# Schematic.net
KiCad netlist of a schematic drawn in EAGLE
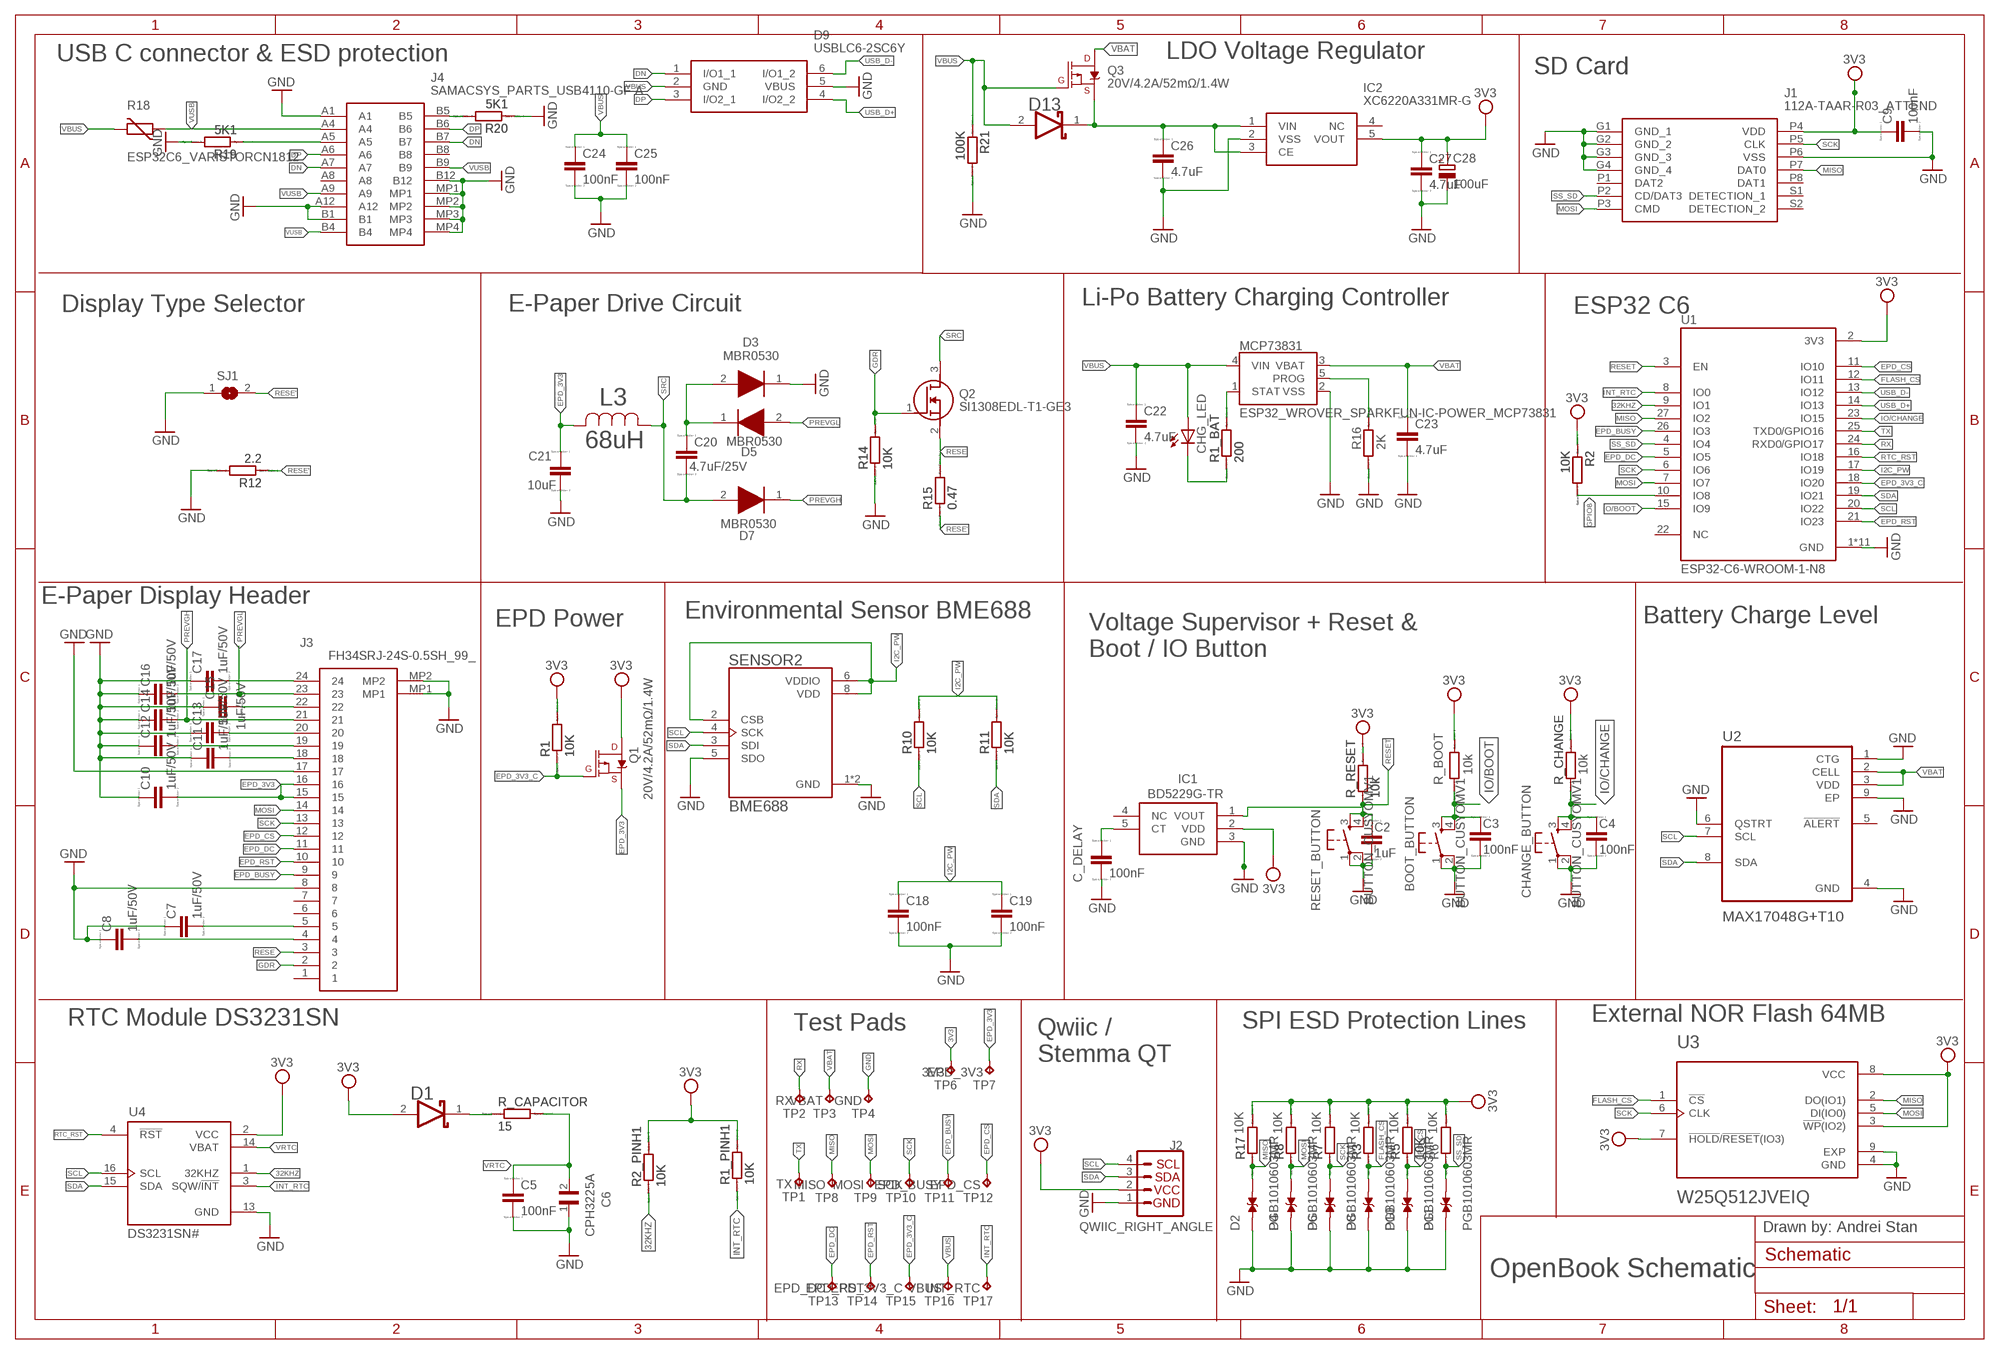
[diagram p0: schematic, sheet 1]

(export (version "E")
  (design (tool "Eeschema 10.0.6"))
  (components
    (comp (ref "BOOT_BUTTON")
      (value "BUTTON_CUSYOMV1")
      (footprint "eagle-import:MYBUTTON")
      (libsource (lib "eagle-import") (part "BUTTON_CUSYOMV1"))
    )
    (comp (ref "C2")
      (value "1uF")
      (footprint "eagle-import:EAGLE-LTSPICE_C0402")
      (libsource (lib "eagle-import") (part "EAGLE-LTSPICE_CC0402"))
    )
    (comp (ref "C3")
      (value "100nF")
      (footprint "eagle-import:EAGLE-LTSPICE_C0402")
      (libsource (lib "eagle-import") (part "EAGLE-LTSPICE_CC0402"))
    )
    (comp (ref "C4")
      (value "100nF")
      (footprint "eagle-import:EAGLE-LTSPICE_C0402")
      (libsource (lib "eagle-import") (part "EAGLE-LTSPICE_CC0402"))
    )
    (comp (ref "C5")
      (value "100nF")
      (footprint "eagle-import:EAGLE-LTSPICE_C0402")
      (libsource (lib "eagle-import") (part "EAGLE-LTSPICE_CC0402"))
    )
    (comp (ref "C6")
      (value "CPH3225A")
      (footprint "eagle-import:CAPCP3225X100N")
      (fields (field (name "MF") "Seiko Instruments"))
      (libsource (lib "eagle-import") (part "CPH3225A"))
    )
    (comp (ref "C7")
      (value "1uF/50V")
      (footprint "eagle-import:EAGLE-LTSPICE_C0402")
      (libsource (lib "eagle-import") (part "EAGLE-LTSPICE_CC0402"))
    )
    (comp (ref "C8")
      (value "1uF/50V")
      (footprint "eagle-import:EAGLE-LTSPICE_C0402")
      (libsource (lib "eagle-import") (part "EAGLE-LTSPICE_CC0402"))
    )
    (comp (ref "C9")
      (value "100nF")
      (footprint "eagle-import:EAGLE-LTSPICE_C0402")
      (libsource (lib "eagle-import") (part "EAGLE-LTSPICE_CC0402"))
    )
    (comp (ref "C10")
      (value "1uF/50V")
      (footprint "eagle-import:EAGLE-LTSPICE_C0402")
      (libsource (lib "eagle-import") (part "EAGLE-LTSPICE_CC0402"))
    )
    (comp (ref "C11")
      (value "1uF/50V")
      (footprint "eagle-import:EAGLE-LTSPICE_C0402")
      (libsource (lib "eagle-import") (part "EAGLE-LTSPICE_CC0402"))
    )
    (comp (ref "C12")
      (value "1uF/50V")
      (footprint "eagle-import:EAGLE-LTSPICE_C0402")
      (libsource (lib "eagle-import") (part "EAGLE-LTSPICE_CC0402"))
    )
    (comp (ref "C13")
      (value "1uF/50V")
      (footprint "eagle-import:EAGLE-LTSPICE_C0402")
      (libsource (lib "eagle-import") (part "EAGLE-LTSPICE_CC0402"))
    )
    (comp (ref "C14")
      (value "1uF/50V")
      (footprint "eagle-import:EAGLE-LTSPICE_C0402")
      (libsource (lib "eagle-import") (part "EAGLE-LTSPICE_CC0402"))
    )
    (comp (ref "C15")
      (value "1uF/50V")
      (footprint "eagle-import:EAGLE-LTSPICE_C0402")
      (libsource (lib "eagle-import") (part "EAGLE-LTSPICE_CC0402"))
    )
    (comp (ref "C16")
      (value "1uF/50V")
      (footprint "eagle-import:EAGLE-LTSPICE_C0402")
      (libsource (lib "eagle-import") (part "EAGLE-LTSPICE_CC0402"))
    )
    (comp (ref "C17")
      (value "1uF/50V")
      (footprint "eagle-import:EAGLE-LTSPICE_C0402")
      (libsource (lib "eagle-import") (part "EAGLE-LTSPICE_CC0402"))
    )
    (comp (ref "C18")
      (value "100nF")
      (footprint "eagle-import:EAGLE-LTSPICE_C0402")
      (libsource (lib "eagle-import") (part "EAGLE-LTSPICE_CC0402"))
    )
    (comp (ref "C19")
      (value "100nF")
      (footprint "eagle-import:EAGLE-LTSPICE_C0402")
      (libsource (lib "eagle-import") (part "EAGLE-LTSPICE_CC0402"))
    )
    (comp (ref "C20")
      (value "4.7uF/25V")
      (footprint "eagle-import:ESP32_WROVER_EAGLE-LTSPICE_C0402")
      (libsource (lib "eagle-import") (part "ESP32_WROVER_EAGLE-LTSPICE_CC0402"))
    )
    (comp (ref "C21")
      (value "10uF")
      (footprint "eagle-import:ESP32_WROVER_EAGLE-LTSPICE_C0402")
      (libsource (lib "eagle-import") (part "ESP32_WROVER_EAGLE-LTSPICE_CC0402"))
    )
    (comp (ref "C22")
      (value "4.7uF")
      (footprint "eagle-import:EAGLE-LTSPICE_C0402")
      (libsource (lib "eagle-import") (part "EAGLE-LTSPICE_CC0402"))
    )
    (comp (ref "C23")
      (value "4.7uF")
      (footprint "eagle-import:EAGLE-LTSPICE_C0402")
      (libsource (lib "eagle-import") (part "EAGLE-LTSPICE_CC0402"))
    )
    (comp (ref "C24")
      (value "100nF")
      (footprint "eagle-import:ESP32_WROVER_EAGLE-LTSPICE_C0402")
      (libsource (lib "eagle-import") (part "ESP32_WROVER_EAGLE-LTSPICE_CC0402"))
    )
    (comp (ref "C25")
      (value "100nF")
      (footprint "eagle-import:ESP32_WROVER_EAGLE-LTSPICE_C0402")
      (libsource (lib "eagle-import") (part "ESP32_WROVER_EAGLE-LTSPICE_CC0402"))
    )
    (comp (ref "C26")
      (value "4.7uF")
      (footprint "eagle-import:ESP32_WROVER_EAGLE-LTSPICE_C0402")
      (libsource (lib "eagle-import") (part "ESP32_WROVER_EAGLE-LTSPICE_CC0402"))
    )
    (comp (ref "C27")
      (value "4.7uF")
      (footprint "eagle-import:ESP32_WROVER_EAGLE-LTSPICE_C0402")
      (libsource (lib "eagle-import") (part "ESP32_WROVER_EAGLE-LTSPICE_CC0402"))
    )
    (comp (ref "C28")
      (value "100uF")
      (footprint "eagle-import:RCL_CT3528")
      (libsource (lib "eagle-import") (part "RCL_CPOL-EUCT3528"))
    )
    (comp (ref "CHANGE_BUTTON")
      (value "BUTTON_CUSYOMV1")
      (footprint "eagle-import:MYBUTTON")
      (libsource (lib "eagle-import") (part "BUTTON_CUSYOMV1"))
    )
    (comp (ref "CHG_LED")
      (value "ADAFRUIT_LEDCHIP-LED0603")
      (footprint "eagle-import:ADAFRUIT_CHIP-LED0603")
      (libsource (lib "eagle-import") (part "ADAFRUIT_LEDCHIP-LED0603"))
    )
    (comp (ref "C_DELAY")
      (value "100nF")
      (footprint "eagle-import:EAGLE-LTSPICE_C0402")
      (libsource (lib "eagle-import") (part "EAGLE-LTSPICE_CC0402"))
    )
    (comp (ref "D1")
      (value "ESP32_WROVER_AVX---SD0805S020S1R0_AVX_SD0805S020S1R0_0_0AVX_SD0805S020S1R0_0_0")
      (footprint "eagle-import:ESP32_WROVER_AVX---SD0805S020S1R0_AVX_SD0805S020S1R0_0")
      (fields
        (field (name "DIGIKEY_PART_NUMBER") "478-7800-1-ND")
        (field (name "MF") "AVX")
        (field (name "MOUSER_PART_NUMBER") "581-SD0805S020S1R0")
      )
      (libsource (lib "eagle-import") (part "ESP32_WROVER_AVX---SD0805S020S1R0_AVX_SD0805S020S1R0_0_0AVX_SD0805S020S1R0_0_0"))
    )
    (comp (ref "D2")
      (value "PGB1010603MR")
      (footprint "eagle-import:DIOC1608X36N")
      (fields (field (name "MF") "Littelfuse Inc."))
      (libsource (lib "eagle-import") (part "PGB1010603MR"))
    )
    (comp (ref "D3")
      (value "MBR0530")
      (footprint "eagle-import:SOD3716X135N")
      (fields (field (name "MF") "ON Semiconductor"))
      (libsource (lib "eagle-import") (part "MBR0530"))
    )
    (comp (ref "D4")
      (value "PGB1010603MR")
      (footprint "eagle-import:DIOC1608X36N")
      (fields (field (name "MF") "Littelfuse Inc."))
      (libsource (lib "eagle-import") (part "PGB1010603MR"))
    )
    (comp (ref "D5")
      (value "MBR0530")
      (footprint "eagle-import:SOD3716X135N")
      (fields (field (name "MF") "ON Semiconductor"))
      (libsource (lib "eagle-import") (part "MBR0530"))
    )
    (comp (ref "D6")
      (value "PGB1010603MR")
      (footprint "eagle-import:DIOC1608X36N")
      (fields (field (name "MF") "Littelfuse Inc."))
      (libsource (lib "eagle-import") (part "PGB1010603MR"))
    )
    (comp (ref "D7")
      (value "MBR0530")
      (footprint "eagle-import:SOD3716X135N")
      (fields (field (name "MF") "ON Semiconductor"))
      (libsource (lib "eagle-import") (part "MBR0530"))
    )
    (comp (ref "D8")
      (value "PGB1010603MR")
      (footprint "eagle-import:DIOC1608X36N")
      (fields (field (name "MF") "Littelfuse Inc."))
      (libsource (lib "eagle-import") (part "PGB1010603MR"))
    )
    (comp (ref "D9")
      (value "USBLC6-2SC6Y")
      (footprint "eagle-import:SOT95P280X145-6N")
      (fields (field (name "MF") "STMicroelectronics"))
      (libsource (lib "eagle-import") (part "USBLC6-2SC6Y"))
    )
    (comp (ref "D10")
      (value "PGB1010603MR")
      (footprint "eagle-import:DIOC1608X36N")
      (fields (field (name "MF") "Littelfuse Inc."))
      (libsource (lib "eagle-import") (part "PGB1010603MR"))
    )
    (comp (ref "D11")
      (value "PGB1010603MR")
      (footprint "eagle-import:DIOC1608X36N")
      (fields (field (name "MF") "Littelfuse Inc."))
      (libsource (lib "eagle-import") (part "PGB1010603MR"))
    )
    (comp (ref "D13")
      (value "ESP32_WROVER_AVX---SD0805S020S1R0_AVX_SD0805S020S1R0_0_0AVX_SD0805S020S1R0_0_0")
      (footprint "eagle-import:ESP32_WROVER_AVX---SD0805S020S1R0_AVX_SD0805S020S1R0_0")
      (fields
        (field (name "DIGIKEY_PART_NUMBER") "478-7800-1-ND")
        (field (name "MF") "AVX")
        (field (name "MOUSER_PART_NUMBER") "581-SD0805S020S1R0")
      )
      (libsource (lib "eagle-import") (part "DeskAssistant v19 v2_vf.c-uWg7zGRE2SlFihlENo6g_ESP32_WROVER_AVX---SD0805S020S1R0_AVX_SD0805S020S1R0_0_0AVX_SD0805S020S1R0_0_0"))
    )
    (comp (ref "IC1")
      (value "BD5229G-TR")
      (footprint "eagle-import:SOT95P280X125-5N")
      (fields (field (name "MOUSER_PART_NUMBER") "755-BD5229G-TR"))
      (libsource (lib "eagle-import") (part "BD5229G-TR"))
    )
    (comp (ref "IC2")
      (value "XC6220A331MR-G")
      (footprint "eagle-import:SOT95P280X120-5N")
      (fields (field (name "MOUSER_PART_NUMBER") "865-XC6220A331MR-G"))
      (libsource (lib "eagle-import") (part "XC6220A331MR-G"))
    )
    (comp (ref "J1")
      (value "112A-TAAR-R03_ATTEND")
      (footprint "eagle-import:112ATAARR03ATTEND")
      (fields (field (name "MANUFACTURER_PART_NUMBER") "112A-TAAR-R03 ATTEND"))
      (libsource (lib "eagle-import") (part "112A-TAAR-R03_ATTEND"))
    )
    (comp (ref "J2")
      (value "QWIIC_RIGHT_ANGLE")
      (footprint "eagle-import:JST04_1MM_RA")
      (libsource (lib "eagle-import") (part "QWIIC_CONNECTORJS-1MM"))
    )
    (comp (ref "J3")
      (value "FH34SRJ-24S-0.5SH_99_")
      (footprint "eagle-import:FH34SRJ24S05SH99")
      (fields
        (field (name "MANUFACTURER_PART_NUMBER") "FH34SRJ-24S-0.5SH(99)")
        (field (name "MOUSER_PART_NUMBER") "798-FH34SRJ24S05SH99")
      )
      (libsource (lib "eagle-import") (part "FH34SRJ-24S-0.5SH_99_"))
    )
    (comp (ref "J4")
      (value "SAMACSYS_PARTS_USB4110-GF-A")
      (footprint "eagle-import:SAMACSYS_PARTS_USB4110GFA")
      (fields
        (field (name "MANUFACTURER_PART_NUMBER") "USB4110-GF-A")
        (field (name "MOUSER_PART_NUMBER") "640-USB4110-GF-A")
      )
      (libsource (lib "eagle-import") (part "SAMACSYS_PARTS_USB4110-GF-A"))
    )
    (comp (ref "L3")
      (value "68uH")
      (footprint "eagle-import:IND_4828-WE-TPC_WRE")
      (fields
        (field (name "MANUFACTURER_PART_NUMBER") "744043680")
        (field (name "COPYRIGHT") "Copyright (C) 2024 Ultra Librarian. All rights reserved.")
      )
      (libsource (lib "eagle-import") (part "744043680IND_4828-WE-TPC_WRE"))
    )
    (comp (ref "MCP73831")
      (value "ESP32_WROVER_SPARKFUN-IC-POWER_MCP73831")
      (footprint "eagle-import:ESP32_WROVER_SPARKFUN-IC-POWER_SOT23-5")
      (libsource (lib "eagle-import") (part "ESP32_WROVER_SPARKFUN-IC-POWER_MCP73831"))
    )
    (comp (ref "Q1")
      (value "20V/4.2A/52mΩ/1.4W")
      (footprint "eagle-import:ESP32_WROVER_SPARKFUN-DISCRETESEMI_SOT23-3")
      (libsource (lib "eagle-import") (part "ESP32_WROVER_SPARKFUN-DISCRETESEMI_MOSFET_PCH-DMG2305UX-7"))
    )
    (comp (ref "Q2")
      (value "SI1308EDL-T1-GE3")
      (footprint "eagle-import:SOT65P210X110-3N")
      (fields (field (name "MF") "Vishay Siliconix"))
      (libsource (lib "eagle-import") (part "SI1308EDL-T1-GE3"))
    )
    (comp (ref "Q3")
      (value "20V/4.2A/52mΩ/1.4W")
      (footprint "eagle-import:ESP32_WROVER_SPARKFUN-DISCRETESEMI_SOT23-3")
      (libsource (lib "eagle-import") (part "DeskAssistant v19 v2_vf.c-uWg7zGRE2SlFihlENo6g_ESP32_WROVER_SPARKFUN-DISCRETESEMI_MOSFET_PCH-DMG2305UX-7"))
    )
    (comp (ref "R1")
      (value "10K")
      (footprint "eagle-import:ESP32_WROVER_EAGLE-LTSPICE_R0402")
      (libsource (lib "eagle-import") (part "ESP32_WROVER_EAGLE-LTSPICE_RR0402"))
    )
    (comp (ref "R1_BAT")
      (value "200")
      (footprint "eagle-import:ESP32_WROVER_EAGLE-LTSPICE_R0402")
      (libsource (lib "eagle-import") (part "ESP32_WROVER_EAGLE-LTSPICE_RR0402"))
    )
    (comp (ref "R1_PINH1")
      (value "10K")
      (footprint "eagle-import:ESP32_WROVER_EAGLE-LTSPICE_R0402")
      (libsource (lib "eagle-import") (part "ESP32_WROVER_EAGLE-LTSPICE_RR0402"))
    )
    (comp (ref "R2")
      (value "10K")
      (footprint "eagle-import:ESP32_WROVER_EAGLE-LTSPICE_R0402")
      (libsource (lib "eagle-import") (part "ESP32_WROVER_EAGLE-LTSPICE_RR0402"))
    )
    (comp (ref "R2_PINH1")
      (value "10K")
      (footprint "eagle-import:ESP32_WROVER_EAGLE-LTSPICE_R0402")
      (libsource (lib "eagle-import") (part "ESP32_WROVER_EAGLE-LTSPICE_RR0402"))
    )
    (comp (ref "R3")
      (value "10K")
      (footprint "eagle-import:ESP32_WROVER_EAGLE-LTSPICE_R0402")
      (libsource (lib "eagle-import") (part "ESP32_WROVER_EAGLE-LTSPICE_RR0402"))
    )
    (comp (ref "R5")
      (value "10K")
      (footprint "eagle-import:ESP32_WROVER_EAGLE-LTSPICE_R0402")
      (libsource (lib "eagle-import") (part "ESP32_WROVER_EAGLE-LTSPICE_RR0402"))
    )
    (comp (ref "R6")
      (value "10K")
      (footprint "eagle-import:ESP32_WROVER_EAGLE-LTSPICE_R0402")
      (libsource (lib "eagle-import") (part "ESP32_WROVER_EAGLE-LTSPICE_RR0402"))
    )
    (comp (ref "R7")
      (value "10K")
      (footprint "eagle-import:ESP32_WROVER_EAGLE-LTSPICE_R0402")
      (libsource (lib "eagle-import") (part "ESP32_WROVER_EAGLE-LTSPICE_RR0402"))
    )
    (comp (ref "R8")
      (value "10K")
      (footprint "eagle-import:ESP32_WROVER_EAGLE-LTSPICE_R0402")
      (libsource (lib "eagle-import") (part "ESP32_WROVER_EAGLE-LTSPICE_RR0402"))
    )
    (comp (ref "R10")
      (value "10K")
      (footprint "eagle-import:ESP32_WROVER_EAGLE-LTSPICE_R0402")
      (libsource (lib "eagle-import") (part "ESP32_WROVER_EAGLE-LTSPICE_RR0402"))
    )
    (comp (ref "R11")
      (value "10K")
      (footprint "eagle-import:ESP32_WROVER_EAGLE-LTSPICE_R0402")
      (libsource (lib "eagle-import") (part "ESP32_WROVER_EAGLE-LTSPICE_RR0402"))
    )
    (comp (ref "R12")
      (value "2.2")
      (footprint "eagle-import:ESP32_WROVER_EAGLE-LTSPICE_R0402")
      (libsource (lib "eagle-import") (part "ESP32_WROVER_EAGLE-LTSPICE_RR0402"))
    )
    (comp (ref "R14")
      (value "10K")
      (footprint "eagle-import:ESP32_WROVER_EAGLE-LTSPICE_R0402")
      (libsource (lib "eagle-import") (part "DeskAssistant v19 v2_vf.c-uWg7zGRE2SlFihlENo6g_ESP32_WROVER_EAGLE-LTSPICE_RR0402"))
    )
    (comp (ref "R15")
      (value "0.47")
      (footprint "eagle-import:ESP32_WROVER_EAGLE-LTSPICE_R0402")
      (libsource (lib "eagle-import") (part "DeskAssistant v19 v2_vf.c-uWg7zGRE2SlFihlENo6g_ESP32_WROVER_EAGLE-LTSPICE_RR0402"))
    )
    (comp (ref "R16")
      (value "2K")
      (footprint "eagle-import:ESP32_WROVER_EAGLE-LTSPICE_R0402")
      (libsource (lib "eagle-import") (part "ESP32_WROVER_EAGLE-LTSPICE_RR0402"))
    )
    (comp (ref "R17")
      (value "10K")
      (footprint "eagle-import:ESP32_WROVER_EAGLE-LTSPICE_R0402")
      (libsource (lib "eagle-import") (part "ESP32_WROVER_EAGLE-LTSPICE_RR0402"))
    )
    (comp (ref "R18")
      (value "ESP32C6_VARISTORCN1812")
      (footprint "eagle-import:ESP32C6_VARISTOR_CT_CN1812")
      (libsource (lib "eagle-import") (part "ESP32C6_VARISTORCN1812"))
    )
    (comp (ref "R19")
      (value "5K1")
      (footprint "eagle-import:ESP32_WROVER_EAGLE-LTSPICE_R0402")
      (libsource (lib "eagle-import") (part "ESP32_WROVER_EAGLE-LTSPICE_RR0402"))
    )
    (comp (ref "R20")
      (value "5K1")
      (footprint "eagle-import:ESP32_WROVER_EAGLE-LTSPICE_R0402")
      (libsource (lib "eagle-import") (part "ESP32_WROVER_EAGLE-LTSPICE_RR0402"))
    )
    (comp (ref "R21")
      (value "100K")
      (footprint "eagle-import:ESP32_WROVER_EAGLE-LTSPICE_R0402")
      (libsource (lib "eagle-import") (part "ESP32_WROVER_EAGLE-LTSPICE_RR0402"))
    )
    (comp (ref "RESET_BUTTON")
      (value "BUTTON_CUSYOMV1")
      (footprint "eagle-import:MYBUTTON")
      (fields
        (field (name "MOUSER_PRICE-STOCK") "https://ro.mouser.com/ProductDetail/Panasonic/EVQ-9P701P?qs=NPkb10g2yLBKCwpELvsGNg%3D%3D")
      )
      (libsource (lib "eagle-import") (part "BUTTON_CUSYOMV1"))
    )
    (comp (ref "R_BOOT")
      (value "10k")
      (footprint "eagle-import:ESP32_WROVER_EAGLE-LTSPICE_R0402")
      (libsource (lib "eagle-import") (part "ESP32_WROVER_EAGLE-LTSPICE_RR0402"))
    )
    (comp (ref "R_CAPACITOR")
      (value "15")
      (footprint "eagle-import:ESP32_WROVER_EAGLE-LTSPICE_R0402")
      (libsource (lib "eagle-import") (part "ESP32_WROVER_EAGLE-LTSPICE_RR0402"))
    )
    (comp (ref "R_CHANGE")
      (value "10k")
      (footprint "eagle-import:ESP32_WROVER_EAGLE-LTSPICE_R0402")
      (libsource (lib "eagle-import") (part "ESP32_WROVER_EAGLE-LTSPICE_RR0402"))
    )
    (comp (ref "R_RESET")
      (value "10k")
      (footprint "eagle-import:ESP32_WROVER_EAGLE-LTSPICE_R0402")
      (libsource (lib "eagle-import") (part "ESP32_WROVER_EAGLE-LTSPICE_RR0402"))
    )
    (comp (ref "SENSOR2")
      (value "BME688")
      (footprint "eagle-import:ESP32_WROVER_BME680_PSON80P300X300X100-8N")
      (fields (field (name "MF") "Bosch Sensortec") (field (name "MP") "BME680"))
      (libsource (lib "eagle-import") (part "ESP32_WROVER_BME680_BME680"))
    )
    (comp (ref "SJ1") (value "SJ") (footprint "eagle-import:SJ") (libsource (lib "eagle-import") (part "SJ")))
    (comp (ref "TP1")
      (value "TPTP20R")
      (footprint "eagle-import:TP20R")
      (fields (field (name "TP_SIGNAL_NAME") "TX"))
      (libsource (lib "eagle-import") (part "TPTP20R"))
    )
    (comp (ref "TP2")
      (value "TPTP20R")
      (footprint "eagle-import:TP20R")
      (fields (field (name "TP_SIGNAL_NAME") "RX"))
      (libsource (lib "eagle-import") (part "TPTP20R"))
    )
    (comp (ref "TP3")
      (value "TPTP20R")
      (footprint "eagle-import:TP20R")
      (fields (field (name "TP_SIGNAL_NAME") "VBAT"))
      (libsource (lib "eagle-import") (part "TPTP20R"))
    )
    (comp (ref "TP4")
      (value "TPTP20R")
      (footprint "eagle-import:TP20R")
      (fields (field (name "TP_SIGNAL_NAME") "GND"))
      (libsource (lib "eagle-import") (part "TPTP20R"))
    )
    (comp (ref "TP6")
      (value "TPTP20R")
      (footprint "eagle-import:TP20R")
      (fields (field (name "TP_SIGNAL_NAME") "3V3"))
      (libsource (lib "eagle-import") (part "TPTP20R"))
    )
    (comp (ref "TP7")
      (value "TPTP20R")
      (footprint "eagle-import:TP20R")
      (fields (field (name "TP_SIGNAL_NAME") "EPD_3V3"))
      (libsource (lib "eagle-import") (part "TPTP20R"))
    )
    (comp (ref "TP8")
      (value "TPTP20R")
      (footprint "eagle-import:TP20R")
      (fields (field (name "TP_SIGNAL_NAME") "MISO"))
      (libsource (lib "eagle-import") (part "TPTP20R"))
    )
    (comp (ref "TP9")
      (value "TPTP20R")
      (footprint "eagle-import:TP20R")
      (fields (field (name "TP_SIGNAL_NAME") "MOSI"))
      (libsource (lib "eagle-import") (part "TPTP20R"))
    )
    (comp (ref "TP10")
      (value "TPTP20R")
      (footprint "eagle-import:TP20R")
      (fields (field (name "TP_SIGNAL_NAME") "SCK"))
      (libsource (lib "eagle-import") (part "TPTP20R"))
    )
    (comp (ref "TP11")
      (value "TPTP20R")
      (footprint "eagle-import:TP20R")
      (fields (field (name "TP_SIGNAL_NAME") "EPD_BUSY"))
      (libsource (lib "eagle-import") (part "TPTP20R"))
    )
    (comp (ref "TP12")
      (value "TPTP20R")
      (footprint "eagle-import:TP20R")
      (fields (field (name "TP_SIGNAL_NAME") "EPD_CS"))
      (libsource (lib "eagle-import") (part "TPTP20R"))
    )
    (comp (ref "TP13")
      (value "TPTP20R")
      (footprint "eagle-import:TP20R")
      (fields (field (name "TP_SIGNAL_NAME") "EPD_DC"))
      (libsource (lib "eagle-import") (part "TPTP20R"))
    )
    (comp (ref "TP14")
      (value "TPTP20R")
      (footprint "eagle-import:TP20R")
      (fields (field (name "TP_SIGNAL_NAME") "EPD_RST"))
      (libsource (lib "eagle-import") (part "TPTP20R"))
    )
    (comp (ref "TP15")
      (value "TPTP20R")
      (footprint "eagle-import:TP20R")
      (fields (field (name "TP_SIGNAL_NAME") "EPD_3V3_C"))
      (libsource (lib "eagle-import") (part "TPTP20R"))
    )
    (comp (ref "TP16")
      (value "TPTP20R")
      (footprint "eagle-import:TP20R")
      (fields (field (name "TP_SIGNAL_NAME") "VBUS"))
      (libsource (lib "eagle-import") (part "TPTP20R"))
    )
    (comp (ref "TP17")
      (value "TPTP20R")
      (footprint "eagle-import:TP20R")
      (fields (field (name "TP_SIGNAL_NAME") "INT_RTC"))
      (libsource (lib "eagle-import") (part "TPTP20R"))
    )
    (comp (ref "U1")
      (value "ESP32-C6-WROOM-1-N8")
      (footprint "eagle-import:XCVR_ESP32-C6-WROOM-1-N8")
      (fields (field (name "MF") "Espressif Systems"))
      (libsource (lib "eagle-import") (part "ESP32-C6-WROOM-1-N8"))
    )
    (comp (ref "U2")
      (value "MAX17048G+T10")
      (footprint "eagle-import:SON50P200X200X80-9N")
      (fields (field (name "MF") "Analog Devices"))
      (libsource (lib "eagle-import") (part "MAX17048G+T10"))
    )
    (comp (ref "U3")
      (value "W25Q512JVEIQ")
      (footprint "eagle-import:SON127P600X800X80-9N")
      (fields (field (name "MF") "Winbond Electronics"))
      (libsource (lib "eagle-import") (part "W25Q512JVEIQ"))
    )
    (comp (ref "U4")
      (value "DS3231SN#")
      (footprint "eagle-import:SOIC127P1032X265-16N")
      (fields (field (name "MF") "Analog Devices"))
      (libsource (lib "eagle-import") (part "DS3231SN#"))
    )
  )
  (nets
    (net (code "1") (name "3V3") (class "Default")
      (node (ref "C27") (pin "1") (pinfunction "1_1") (pintype "passive"))
      (node (ref "C28") (pin "+") (pinfunction "+_+") (pintype "passive"))
      (node (ref "C9") (pin "1") (pinfunction "1_1") (pintype "passive"))
      (node (ref "D1") (pin "2") (pinfunction "ANODE_2") (pintype "bidirectional"))
      (node (ref "IC1") (pin "2") (pinfunction "VDD_2") (pintype "bidirectional"))
      (node (ref "IC2") (pin "5") (pinfunction "VOUT_5") (pintype "bidirectional"))
      (node (ref "J1") (pin "P4") (pinfunction "VDD_P4") (pintype "bidirectional"))
      (node (ref "J2") (pin "2") (pinfunction "2_2") (pintype "power_in"))
      (node (ref "Q1") (pin "3") (pinfunction "D_3") (pintype "bidirectional"))
      (node (ref "R1") (pin "2") (pinfunction "2_2") (pintype "passive"))
      (node (ref "R17") (pin "2") (pinfunction "2_2") (pintype "passive"))
      (node (ref "R1_PINH1") (pin "2") (pinfunction "2_2") (pintype "passive"))
      (node (ref "R2") (pin "1") (pinfunction "1_1") (pintype "passive"))
      (node (ref "R2_PINH1") (pin "2") (pinfunction "2_2") (pintype "passive"))
      (node (ref "R3") (pin "2") (pinfunction "2_2") (pintype "passive"))
      (node (ref "R5") (pin "2") (pinfunction "2_2") (pintype "passive"))
      (node (ref "R6") (pin "2") (pinfunction "2_2") (pintype "passive"))
      (node (ref "R7") (pin "2") (pinfunction "2_2") (pintype "passive"))
      (node (ref "R8") (pin "2") (pinfunction "2_2") (pintype "passive"))
      (node (ref "R_BOOT") (pin "2") (pinfunction "2_2") (pintype "passive"))
      (node (ref "R_CHANGE") (pin "2") (pinfunction "2_2") (pintype "passive"))
      (node (ref "R_RESET") (pin "2") (pinfunction "2_2") (pintype "passive"))
      (node (ref "TP6") (pin "TP") (pinfunction "TP_TP") (pintype "input"))
      (node (ref "U1") (pin "2") (pinfunction "3V3_2") (pintype "power_in"))
      (node (ref "U3") (pin "3") (pinfunction "~{WP}(IO2)_3") (pintype "bidirectional"))
      (node (ref "U3") (pin "7") (pinfunction "~{HOLD}/~{RESET}(IO3)_7") (pintype "bidirectional"))
      (node (ref "U3") (pin "8") (pinfunction "VCC_8") (pintype "power_in"))
      (node (ref "U4") (pin "2") (pinfunction "VCC_2") (pintype "power_in"))
    )
    (net (code "2") (name "32KHZ") (class "Default")
      (node (ref "R2_PINH1") (pin "1") (pinfunction "1_1") (pintype "passive"))
      (node (ref "U1") (pin "9") (pinfunction "IO1_9") (pintype "bidirectional"))
      (node (ref "U4") (pin "1") (pinfunction "32KHZ_1") (pintype "output"))
    )
    (net (code "3") (name "DN") (class "Default")
      (node (ref "D9") (pin "1") (pinfunction "I/O1_1_1") (pintype "bidirectional"))
      (node (ref "J4") (pin "A7") (pinfunction "A7_A7") (pintype "bidirectional"))
      (node (ref "J4") (pin "B7") (pinfunction "B7_B7") (pintype "bidirectional"))
    )
    (net (code "4") (name "DP") (class "Default")
      (node (ref "D9") (pin "3") (pinfunction "I/O2_1_3") (pintype "bidirectional"))
      (node (ref "J4") (pin "A6") (pinfunction "A6_A6") (pintype "bidirectional"))
      (node (ref "J4") (pin "B6") (pinfunction "B6_B6") (pintype "bidirectional"))
    )
    (net (code "5") (name "EPD_3V3") (class "Default")
      (node (ref "C10") (pin "2") (pinfunction "2_2") (pintype "passive"))
      (node (ref "C21") (pin "1") (pinfunction "1_1") (pintype "passive"))
      (node (ref "J3") (pin "15") (pinfunction "15_15") (pintype "bidirectional"))
      (node (ref "J3") (pin "16") (pinfunction "16_16") (pintype "bidirectional"))
      (node (ref "L3") (pin "2") (pinfunction "2_2") (pintype "passive"))
      (node (ref "Q1") (pin "2") (pinfunction "S_2") (pintype "bidirectional"))
      (node (ref "TP7") (pin "TP") (pinfunction "TP_TP") (pintype "input"))
    )
    (net (code "6") (name "EPD_3V3_C") (class "Default")
      (node (ref "Q1") (pin "1") (pinfunction "G_1") (pintype "bidirectional"))
      (node (ref "R1") (pin "1") (pinfunction "1_1") (pintype "passive"))
      (node (ref "TP15") (pin "TP") (pinfunction "TP_TP") (pintype "input"))
      (node (ref "U1") (pin "18") (pinfunction "IO20_18") (pintype "bidirectional"))
    )
    (net (code "7") (name "EPD_BUSY") (class "Default")
      (node (ref "J3") (pin "9") (pinfunction "9_9") (pintype "bidirectional"))
      (node (ref "TP11") (pin "TP") (pinfunction "TP_TP") (pintype "input"))
      (node (ref "U1") (pin "26") (pinfunction "IO3_26") (pintype "bidirectional"))
    )
    (net (code "8") (name "EPD_CS") (class "Default")
      (node (ref "D10") (pin "2") (pinfunction "2_2") (pintype "passive"))
      (node (ref "J3") (pin "12") (pinfunction "12_12") (pintype "bidirectional"))
      (node (ref "R5") (pin "1") (pinfunction "1_1") (pintype "passive"))
      (node (ref "TP12") (pin "TP") (pinfunction "TP_TP") (pintype "input"))
      (node (ref "U1") (pin "11") (pinfunction "IO10_11") (pintype "bidirectional"))
    )
    (net (code "9") (name "EPD_DC") (class "Default")
      (node (ref "J3") (pin "11") (pinfunction "11_11") (pintype "bidirectional"))
      (node (ref "TP13") (pin "TP") (pinfunction "TP_TP") (pintype "input"))
      (node (ref "U1") (pin "5") (pinfunction "IO5_5") (pintype "bidirectional"))
    )
    (net (code "10") (name "EPD_RST") (class "Default")
      (node (ref "J3") (pin "10") (pinfunction "10_10") (pintype "bidirectional"))
      (node (ref "TP14") (pin "TP") (pinfunction "TP_TP") (pintype "input"))
      (node (ref "U1") (pin "21") (pinfunction "IO23_21") (pintype "bidirectional"))
    )
    (net (code "11") (name "FLASH_CS") (class "Default")
      (node (ref "D8") (pin "2") (pinfunction "2_2") (pintype "passive"))
      (node (ref "R3") (pin "1") (pinfunction "1_1") (pintype "passive"))
      (node (ref "U1") (pin "12") (pinfunction "IO11_12") (pintype "bidirectional"))
      (node (ref "U3") (pin "1") (pinfunction "~{CS}_1") (pintype "input"))
    )
    (net (code "12") (name "GDR") (class "Default")
      (node (ref "J3") (pin "2") (pinfunction "2_2") (pintype "bidirectional"))
      (node (ref "Q2") (pin "1") (pinfunction "G_1") (pintype "bidirectional"))
      (node (ref "R14") (pin "2") (pinfunction "2_2") (pintype "passive"))
    )
    (net (code "13") (name "GND") (class "Default")
      (node (ref "BOOT_BUTTON") (pin "1") (pinfunction "1_1") (pintype "passive"))
      (node (ref "BOOT_BUTTON") (pin "2") (pinfunction "2_2") (pintype "passive"))
      (node (ref "C10") (pin "1") (pinfunction "1_1") (pintype "passive"))
      (node (ref "C11") (pin "1") (pinfunction "1_1") (pintype "passive"))
      (node (ref "C12") (pin "1") (pinfunction "1_1") (pintype "passive"))
      (node (ref "C13") (pin "1") (pinfunction "1_1") (pintype "passive"))
      (node (ref "C14") (pin "1") (pinfunction "1_1") (pintype "passive"))
      (node (ref "C15") (pin "1") (pinfunction "1_1") (pintype "passive"))
      (node (ref "C16") (pin "1") (pinfunction "1_1") (pintype "passive"))
      (node (ref "C17") (pin "1") (pinfunction "1_1") (pintype "passive"))
      (node (ref "C18") (pin "2") (pinfunction "2_2") (pintype "passive"))
      (node (ref "C19") (pin "2") (pinfunction "2_2") (pintype "passive"))
      (node (ref "C2") (pin "2") (pinfunction "2_2") (pintype "passive"))
      (node (ref "C21") (pin "2") (pinfunction "2_2") (pintype "passive"))
      (node (ref "C22") (pin "2") (pinfunction "2_2") (pintype "passive"))
      (node (ref "C23") (pin "2") (pinfunction "2_2") (pintype "passive"))
      (node (ref "C24") (pin "2") (pinfunction "2_2") (pintype "passive"))
      (node (ref "C25") (pin "2") (pinfunction "2_2") (pintype "passive"))
      (node (ref "C26") (pin "2") (pinfunction "2_2") (pintype "passive"))
      (node (ref "C27") (pin "2") (pinfunction "2_2") (pintype "passive"))
      (node (ref "C28") (pin "-") (pinfunction "-_-") (pintype "passive"))
      (node (ref "C3") (pin "2") (pinfunction "2_2") (pintype "passive"))
      (node (ref "C4") (pin "2") (pinfunction "2_2") (pintype "passive"))
      (node (ref "C5") (pin "2") (pinfunction "2_2") (pintype "passive"))
      (node (ref "C6") (pin "1") (pinfunction "1_1") (pintype "passive"))
      (node (ref "C7") (pin "1") (pinfunction "1_1") (pintype "passive"))
      (node (ref "C8") (pin "1") (pinfunction "1_1") (pintype "passive"))
      (node (ref "C9") (pin "2") (pinfunction "2_2") (pintype "passive"))
      (node (ref "CHANGE_BUTTON") (pin "1") (pinfunction "1_1") (pintype "passive"))
      (node (ref "CHANGE_BUTTON") (pin "2") (pinfunction "2_2") (pintype "passive"))
      (node (ref "C_DELAY") (pin "2") (pinfunction "2_2") (pintype "passive"))
      (node (ref "D10") (pin "1") (pinfunction "1_1") (pintype "passive"))
      (node (ref "D11") (pin "1") (pinfunction "1_1") (pintype "passive"))
      (node (ref "D2") (pin "1") (pinfunction "1_1") (pintype "passive"))
      (node (ref "D3") (pin "1") (pinfunction "K_1") (pintype "bidirectional"))
      (node (ref "D4") (pin "1") (pinfunction "1_1") (pintype "passive"))
      (node (ref "D6") (pin "1") (pinfunction "1_1") (pintype "passive"))
      (node (ref "D8") (pin "1") (pinfunction "1_1") (pintype "passive"))
      (node (ref "D9") (pin "5") (pinfunction "VBUS_5") (pintype "bidirectional"))
      (node (ref "IC1") (pin "3") (pinfunction "GND_3") (pintype "bidirectional"))
      (node (ref "IC2") (pin "2") (pinfunction "VSS_2") (pintype "bidirectional"))
      (node (ref "J1") (pin "G1") (pinfunction "GND_1_G1") (pintype "bidirectional"))
      (node (ref "J1") (pin "G2") (pinfunction "GND_2_G2") (pintype "bidirectional"))
      (node (ref "J1") (pin "G3") (pinfunction "GND_3_G3") (pintype "bidirectional"))
      (node (ref "J1") (pin "G4") (pinfunction "GND_4_G4") (pintype "bidirectional"))
      (node (ref "J1") (pin "P6") (pinfunction "VSS_P6") (pintype "bidirectional"))
      (node (ref "J2") (pin "1") (pinfunction "1_1") (pintype "power_in"))
      (node (ref "J3") (pin "17") (pinfunction "17_17") (pintype "bidirectional"))
      (node (ref "J3") (pin "8") (pinfunction "8_8") (pintype "bidirectional"))
      (node (ref "J3") (pin "MP1") (pinfunction "MP1_MP1") (pintype "bidirectional"))
      (node (ref "J3") (pin "MP2") (pinfunction "MP2_MP2") (pintype "bidirectional"))
      (node (ref "J4") (pin "A1") (pinfunction "A1_A1") (pintype "bidirectional"))
      (node (ref "J4") (pin "A12") (pinfunction "A12_A12") (pintype "bidirectional"))
      (node (ref "J4") (pin "B1") (pinfunction "B1_B1") (pintype "bidirectional"))
      (node (ref "J4") (pin "B12") (pinfunction "B12_B12") (pintype "bidirectional"))
      (node (ref "J4") (pin "MP1") (pinfunction "MP1_MP1") (pintype "bidirectional"))
      (node (ref "J4") (pin "MP2") (pinfunction "MP2_MP2") (pintype "bidirectional"))
      (node (ref "J4") (pin "MP3") (pinfunction "MP3_MP3") (pintype "bidirectional"))
      (node (ref "J4") (pin "MP4") (pinfunction "MP4_MP4") (pintype "bidirectional"))
      (node (ref "MCP73831") (pin "2") (pinfunction "VSS_2") (pintype "power_in"))
      (node (ref "R12") (pin "2") (pinfunction "2_2") (pintype "passive"))
      (node (ref "R14") (pin "1") (pinfunction "1_1") (pintype "passive"))
      (node (ref "R16") (pin "1") (pinfunction "1_1") (pintype "passive"))
      (node (ref "R19") (pin "2") (pinfunction "2_2") (pintype "passive"))
      (node (ref "R20") (pin "1") (pinfunction "1_1") (pintype "passive"))
      (node (ref "R21") (pin "2") (pinfunction "2_2") (pintype "passive"))
      (node (ref "RESET_BUTTON") (pin "1") (pinfunction "1_1") (pintype "passive"))
      (node (ref "RESET_BUTTON") (pin "2") (pinfunction "2_2") (pintype "passive"))
      (node (ref "SENSOR2") (pin "1") (pinfunction "GND_1") (pintype "power_in"))
      (node (ref "SENSOR2") (pin "5") (pinfunction "SDO_5") (pintype "bidirectional"))
      (node (ref "SENSOR2") (pin "7") (pinfunction "GND_7") (pintype "power_in"))
      (node (ref "SJ1") (pin "1") (pinfunction "1_1") (pintype "passive"))
      (node (ref "TP4") (pin "TP") (pinfunction "TP_TP") (pintype "input"))
      (node (ref "U1") (pin "1") (pinfunction "GND_1") (pintype "power_in"))
      (node (ref "U1") (pin "28") (pinfunction "GND_28") (pintype "power_in"))
      (node (ref "U1") (pin "29_1") (pinfunction "GND_29_1") (pintype "power_in"))
      (node (ref "U1") (pin "29_2") (pinfunction "GND_29_2") (pintype "power_in"))
      (node (ref "U1") (pin "29_3") (pinfunction "GND_29_3") (pintype "power_in"))
      (node (ref "U1") (pin "29_4") (pinfunction "GND_29_4") (pintype "power_in"))
      (node (ref "U1") (pin "29_5") (pinfunction "GND_29_5") (pintype "power_in"))
      (node (ref "U1") (pin "29_6") (pinfunction "GND_29_6") (pintype "power_in"))
      (node (ref "U1") (pin "29_7") (pinfunction "GND_29_7") (pintype "power_in"))
      (node (ref "U1") (pin "29_8") (pinfunction "GND_29_8") (pintype "power_in"))
      (node (ref "U1") (pin "29_9") (pinfunction "GND_29_9") (pintype "power_in"))
      (node (ref "U2") (pin "1") (pinfunction "CTG_1") (pintype "power_in"))
      (node (ref "U2") (pin "4") (pinfunction "GND_4") (pintype "power_in"))
      (node (ref "U2") (pin "6") (pinfunction "QSTRT_6") (pintype "input"))
      (node (ref "U2") (pin "9") (pinfunction "EP_9") (pintype "power_in"))
      (node (ref "U3") (pin "4") (pinfunction "GND_4") (pintype "power_in"))
      (node (ref "U3") (pin "9") (pinfunction "EXP_9") (pintype "passive"))
      (node (ref "U4") (pin "13") (pinfunction "GND_13") (pintype "power_in"))
    )
    (net (code "14") (name "GPIO8") (class "Default")
      (node (ref "R2") (pin "2") (pinfunction "2_2") (pintype "passive"))
      (node (ref "U1") (pin "10") (pinfunction "IO8_10") (pintype "bidirectional"))
    )
    (net (code "15") (name "I2C_PW") (class "Default")
      (node (ref "C18") (pin "1") (pinfunction "1_1") (pintype "passive"))
      (node (ref "C19") (pin "1") (pinfunction "1_1") (pintype "passive"))
      (node (ref "R10") (pin "2") (pinfunction "2_2") (pintype "passive"))
      (node (ref "R11") (pin "2") (pinfunction "2_2") (pintype "passive"))
      (node (ref "SENSOR2") (pin "2") (pinfunction "CSB_2") (pintype "input"))
      (node (ref "SENSOR2") (pin "6") (pinfunction "VDDIO_6") (pintype "power_in"))
      (node (ref "SENSOR2") (pin "8") (pinfunction "VDD_8") (pintype "power_in"))
      (node (ref "U1") (pin "17") (pinfunction "IO19_17") (pintype "bidirectional"))
    )
    (net (code "16") (name "INT_RTC") (class "Default")
      (node (ref "R1_PINH1") (pin "1") (pinfunction "1_1") (pintype "passive"))
      (node (ref "TP17") (pin "TP") (pinfunction "TP_TP") (pintype "input"))
      (node (ref "U1") (pin "8") (pinfunction "IO0_8") (pintype "bidirectional"))
      (node (ref "U4") (pin "3") (pinfunction "SQW/~{INT}_3") (pintype "output"))
    )
    (net (code "17") (name "IO{slash}BOOT") (class "Default")
      (node (ref "BOOT_BUTTON") (pin "3") (pinfunction "3_3") (pintype "passive"))
      (node (ref "BOOT_BUTTON") (pin "4") (pinfunction "4_4") (pintype "passive"))
      (node (ref "C3") (pin "1") (pinfunction "1_1") (pintype "passive"))
      (node (ref "R_BOOT") (pin "1") (pinfunction "1_1") (pintype "passive"))
      (node (ref "U1") (pin "15") (pinfunction "IO9_15") (pintype "bidirectional"))
    )
    (net (code "18") (name "IO{slash}CHANGE") (class "Default")
      (node (ref "C4") (pin "1") (pinfunction "1_1") (pintype "passive"))
      (node (ref "CHANGE_BUTTON") (pin "3") (pinfunction "3_3") (pintype "passive"))
      (node (ref "CHANGE_BUTTON") (pin "4") (pinfunction "4_4") (pintype "passive"))
      (node (ref "R_CHANGE") (pin "1") (pinfunction "1_1") (pintype "passive"))
      (node (ref "U1") (pin "23") (pinfunction "IO15_23") (pintype "bidirectional"))
    )
    (net (code "19") (name "MISO") (class "Default")
      (node (ref "D2") (pin "2") (pinfunction "2_2") (pintype "passive"))
      (node (ref "J1") (pin "P7") (pinfunction "DAT0_P7") (pintype "bidirectional"))
      (node (ref "R17") (pin "1") (pinfunction "1_1") (pintype "passive"))
      (node (ref "TP8") (pin "TP") (pinfunction "TP_TP") (pintype "input"))
      (node (ref "U1") (pin "27") (pinfunction "IO2_27") (pintype "bidirectional"))
      (node (ref "U3") (pin "2") (pinfunction "DO(IO1)_2") (pintype "bidirectional"))
    )
    (net (code "20") (name "MOSI") (class "Default")
      (node (ref "D4") (pin "2") (pinfunction "2_2") (pintype "passive"))
      (node (ref "J1") (pin "P3") (pinfunction "CMD_P3") (pintype "bidirectional"))
      (node (ref "J3") (pin "14") (pinfunction "14_14") (pintype "bidirectional"))
      (node (ref "R8") (pin "1") (pinfunction "1_1") (pintype "passive"))
      (node (ref "TP9") (pin "TP") (pinfunction "TP_TP") (pintype "input"))
      (node (ref "U1") (pin "7") (pinfunction "IO7_7") (pintype "bidirectional"))
      (node (ref "U3") (pin "5") (pinfunction "DI(IO0)_5") (pintype "bidirectional"))
    )
    (net (code "21") (name "Net-(C7-Pad2)") (class "Default")
      (node (ref "C7") (pin "2") (pinfunction "2_2") (pintype "passive"))
      (node (ref "J3") (pin "5") (pinfunction "5_5") (pintype "bidirectional"))
    )
    (net (code "22") (name "Net-(C8-Pad2)") (class "Default")
      (node (ref "C8") (pin "2") (pinfunction "2_2") (pintype "passive"))
      (node (ref "J3") (pin "4") (pinfunction "4_4") (pintype "bidirectional"))
    )
    (net (code "23") (name "Net-(C11-Pad2)") (class "Default")
      (node (ref "C11") (pin "2") (pinfunction "2_2") (pintype "passive"))
      (node (ref "J3") (pin "18") (pinfunction "18_18") (pintype "bidirectional"))
    )
    (net (code "24") (name "Net-(C12-Pad2)") (class "Default")
      (node (ref "C12") (pin "2") (pinfunction "2_2") (pintype "passive"))
      (node (ref "J3") (pin "19") (pinfunction "19_19") (pintype "bidirectional"))
    )
    (net (code "25") (name "Net-(C13-Pad2)") (class "Default")
      (node (ref "C13") (pin "2") (pinfunction "2_2") (pintype "passive"))
      (node (ref "J3") (pin "20") (pinfunction "20_20") (pintype "bidirectional"))
    )
    (net (code "26") (name "Net-(C15-Pad2)") (class "Default")
      (node (ref "C15") (pin "2") (pinfunction "2_2") (pintype "passive"))
      (node (ref "J3") (pin "22") (pinfunction "22_22") (pintype "bidirectional"))
    )
    (net (code "27") (name "Net-(C17-Pad2)") (class "Default")
      (node (ref "C17") (pin "2") (pinfunction "2_2") (pintype "passive"))
      (node (ref "J3") (pin "24") (pinfunction "24_24") (pintype "bidirectional"))
    )
    (net (code "28") (name "Net-(CHG_LED-PadC)") (class "Default")
      (node (ref "CHG_LED") (pin "C") (pinfunction "C_C") (pintype "passive"))
      (node (ref "R1_BAT") (pin "1") (pinfunction "1_1") (pintype "passive"))
    )
    (net (code "29") (name "Net-(D1-CATHODE)") (class "Default")
      (node (ref "D1") (pin "1") (pinfunction "CATHODE_1") (pintype "bidirectional"))
      (node (ref "R_CAPACITOR") (pin "1") (pinfunction "1_1") (pintype "passive"))
    )
    (net (code "30") (name "Net-(D3-A)") (class "Default")
      (node (ref "C20") (pin "1") (pinfunction "1_1") (pintype "passive"))
      (node (ref "D3") (pin "2") (pinfunction "A_2") (pintype "bidirectional"))
      (node (ref "D5") (pin "1") (pinfunction "K_1") (pintype "bidirectional"))
    )
    (net (code "31") (name "Net-(D13-CATHODE)") (class "Default")
      (node (ref "C26") (pin "1") (pinfunction "1_1") (pintype "passive"))
      (node (ref "D13") (pin "1") (pinfunction "CATHODE_1") (pintype "bidirectional"))
      (node (ref "IC2") (pin "1") (pinfunction "VIN_1") (pintype "bidirectional"))
      (node (ref "IC2") (pin "3") (pinfunction "CE_3") (pintype "bidirectional"))
      (node (ref "Q3") (pin "2") (pinfunction "S_2") (pintype "bidirectional"))
    )
    (net (code "32") (name "Net-(IC1-CT)") (class "Default")
      (node (ref "C_DELAY") (pin "1") (pinfunction "1_1") (pintype "passive"))
      (node (ref "IC1") (pin "5") (pinfunction "CT_5") (pintype "bidirectional"))
    )
    (net (code "33") (name "Net-(J4-PadA5)") (class "Default")
      (node (ref "J4") (pin "A5") (pinfunction "A5_A5") (pintype "bidirectional"))
      (node (ref "R19") (pin "1") (pinfunction "1_1") (pintype "passive"))
    )
    (net (code "34") (name "Net-(J4-PadB5)") (class "Default")
      (node (ref "J4") (pin "B5") (pinfunction "B5_B5") (pintype "bidirectional"))
      (node (ref "R20") (pin "2") (pinfunction "2_2") (pintype "passive"))
    )
    (net (code "35") (name "Net-(MCP73831-PROG)") (class "Default")
      (node (ref "MCP73831") (pin "5") (pinfunction "PROG_5") (pintype "input"))
      (node (ref "R16") (pin "2") (pinfunction "2_2") (pintype "passive"))
    )
    (net (code "36") (name "Net-(MCP73831-STAT)") (class "Default")
      (node (ref "MCP73831") (pin "1") (pinfunction "STAT_1") (pintype "output"))
      (node (ref "R1_BAT") (pin "2") (pinfunction "2_2") (pintype "passive"))
    )
    (net (code "37") (name "PREVGH") (class "Default")
      (node (ref "C14") (pin "2") (pinfunction "2_2") (pintype "passive"))
      (node (ref "D7") (pin "1") (pinfunction "K_1") (pintype "bidirectional"))
      (node (ref "J3") (pin "21") (pinfunction "21_21") (pintype "bidirectional"))
    )
    (net (code "38") (name "PREVGL") (class "Default")
      (node (ref "C16") (pin "2") (pinfunction "2_2") (pintype "passive"))
      (node (ref "D5") (pin "2") (pinfunction "A_2") (pintype "bidirectional"))
      (node (ref "J3") (pin "23") (pinfunction "23_23") (pintype "bidirectional"))
    )
    (net (code "39") (name "RESE") (class "Default")
      (node (ref "J3") (pin "3") (pinfunction "3_3") (pintype "bidirectional"))
      (node (ref "Q2") (pin "2") (pinfunction "S_2") (pintype "bidirectional"))
      (node (ref "R15") (pin "2") (pinfunction "2_2") (pintype "passive"))
    )
    (net (code "40") (name "RESE'") (class "Default")
      (node (ref "R12") (pin "1") (pinfunction "1_1") (pintype "passive"))
      (node (ref "R15") (pin "1") (pinfunction "1_1") (pintype "passive"))
      (node (ref "SJ1") (pin "2") (pinfunction "2_2") (pintype "passive"))
    )
    (net (code "41") (name "RESET") (class "Default")
      (node (ref "C2") (pin "1") (pinfunction "1_1") (pintype "passive"))
      (node (ref "IC1") (pin "1") (pinfunction "VOUT_1") (pintype "bidirectional"))
      (node (ref "RESET_BUTTON") (pin "3") (pinfunction "3_3") (pintype "passive"))
      (node (ref "RESET_BUTTON") (pin "4") (pinfunction "4_4") (pintype "passive"))
      (node (ref "R_RESET") (pin "1") (pinfunction "1_1") (pintype "passive"))
      (node (ref "U1") (pin "3") (pinfunction "EN_3") (pintype "input"))
    )
    (net (code "42") (name "RTC_RST") (class "Default")
      (node (ref "U1") (pin "16") (pinfunction "IO18_16") (pintype "bidirectional"))
      (node (ref "U4") (pin "4") (pinfunction "~{RST}_4") (pintype "input"))
    )
    (net (code "43") (name "RX") (class "Default")
      (node (ref "TP2") (pin "TP") (pinfunction "TP_TP") (pintype "input"))
      (node (ref "U1") (pin "24") (pinfunction "RXD0/GPIO17_24") (pintype "bidirectional"))
    )
    (net (code "44") (name "SCK") (class "Default")
      (node (ref "D6") (pin "2") (pinfunction "2_2") (pintype "passive"))
      (node (ref "J1") (pin "P5") (pinfunction "CLK_P5") (pintype "bidirectional"))
      (node (ref "J3") (pin "13") (pinfunction "13_13") (pintype "bidirectional"))
      (node (ref "R7") (pin "1") (pinfunction "1_1") (pintype "passive"))
      (node (ref "TP10") (pin "TP") (pinfunction "TP_TP") (pintype "input"))
      (node (ref "U1") (pin "6") (pinfunction "IO6_6") (pintype "bidirectional"))
      (node (ref "U3") (pin "6") (pinfunction "CLK_6") (pintype "input"))
    )
    (net (code "45") (name "SCL") (class "Default")
      (node (ref "J2") (pin "4") (pinfunction "4_4") (pintype "passive"))
      (node (ref "R10") (pin "1") (pinfunction "1_1") (pintype "passive"))
      (node (ref "SENSOR2") (pin "4") (pinfunction "SCK_4") (pintype "input"))
      (node (ref "U1") (pin "20") (pinfunction "IO22_20") (pintype "bidirectional"))
      (node (ref "U2") (pin "7") (pinfunction "SCL_7") (pintype "input"))
      (node (ref "U4") (pin "16") (pinfunction "SCL_16") (pintype "input"))
    )
    (net (code "46") (name "SDA") (class "Default")
      (node (ref "J2") (pin "3") (pinfunction "3_3") (pintype "passive"))
      (node (ref "R11") (pin "1") (pinfunction "1_1") (pintype "passive"))
      (node (ref "SENSOR2") (pin "3") (pinfunction "SDI_3") (pintype "bidirectional"))
      (node (ref "U1") (pin "19") (pinfunction "IO21_19") (pintype "bidirectional"))
      (node (ref "U2") (pin "8") (pinfunction "SDA_8") (pintype "bidirectional"))
      (node (ref "U4") (pin "15") (pinfunction "SDA_15") (pintype "bidirectional"))
    )
    (net (code "47") (name "SRC") (class "Default")
      (node (ref "C20") (pin "2") (pinfunction "2_2") (pintype "passive"))
      (node (ref "D7") (pin "2") (pinfunction "A_2") (pintype "bidirectional"))
      (node (ref "L3") (pin "1") (pinfunction "1_1") (pintype "passive"))
      (node (ref "Q2") (pin "3") (pinfunction "D_3") (pintype "bidirectional"))
    )
    (net (code "48") (name "SS_SD") (class "Default")
      (node (ref "D11") (pin "2") (pinfunction "2_2") (pintype "passive"))
      (node (ref "J1") (pin "P2") (pinfunction "CD/DAT3_P2") (pintype "bidirectional"))
      (node (ref "R6") (pin "1") (pinfunction "1_1") (pintype "passive"))
      (node (ref "U1") (pin "4") (pinfunction "IO4_4") (pintype "bidirectional"))
    )
    (net (code "49") (name "TX") (class "Default")
      (node (ref "TP1") (pin "TP") (pinfunction "TP_TP") (pintype "input"))
      (node (ref "U1") (pin "25") (pinfunction "TXD0/GPIO16_25") (pintype "bidirectional"))
    )
    (net (code "50") (name "USB_D+") (class "Default")
      (node (ref "D9") (pin "4") (pinfunction "I/O2_2_4") (pintype "bidirectional"))
      (node (ref "U1") (pin "14") (pinfunction "IO13_14") (pintype "bidirectional"))
    )
    (net (code "51") (name "USB_D-") (class "Default")
      (node (ref "D9") (pin "6") (pinfunction "I/O1_2_6") (pintype "bidirectional"))
      (node (ref "U1") (pin "13") (pinfunction "IO12_13") (pintype "bidirectional"))
    )
    (net (code "52") (name "VBAT") (class "Default")
      (node (ref "C23") (pin "1") (pinfunction "1_1") (pintype "passive"))
      (node (ref "MCP73831") (pin "3") (pinfunction "VBAT_3") (pintype "power_in"))
      (node (ref "Q3") (pin "3") (pinfunction "D_3") (pintype "bidirectional"))
      (node (ref "TP3") (pin "TP") (pinfunction "TP_TP") (pintype "input"))
      (node (ref "U2") (pin "2") (pinfunction "CELL_2") (pintype "power_in"))
      (node (ref "U2") (pin "3") (pinfunction "VDD_3") (pintype "power_in"))
    )
    (net (code "53") (name "VBUS") (class "Default")
      (node (ref "C22") (pin "1") (pinfunction "1_1") (pintype "passive"))
      (node (ref "C24") (pin "1") (pinfunction "1_1") (pintype "passive"))
      (node (ref "C25") (pin "1") (pinfunction "1_1") (pintype "passive"))
      (node (ref "CHG_LED") (pin "A") (pinfunction "A_A") (pintype "passive"))
      (node (ref "D13") (pin "2") (pinfunction "ANODE_2") (pintype "bidirectional"))
      (node (ref "D9") (pin "2") (pinfunction "GND_2") (pintype "bidirectional"))
      (node (ref "MCP73831") (pin "4") (pinfunction "VIN_4") (pintype "power_in"))
      (node (ref "Q3") (pin "1") (pinfunction "G_1") (pintype "bidirectional"))
      (node (ref "R18") (pin "2") (pinfunction "2_2") (pintype "passive"))
      (node (ref "R21") (pin "1") (pinfunction "1_1") (pintype "passive"))
      (node (ref "TP16") (pin "TP") (pinfunction "TP_TP") (pintype "input"))
    )
    (net (code "54") (name "VRTC") (class "Default")
      (node (ref "C5") (pin "1") (pinfunction "1_1") (pintype "passive"))
      (node (ref "C6") (pin "2") (pinfunction "2_2") (pintype "passive"))
      (node (ref "R_CAPACITOR") (pin "2") (pinfunction "2_2") (pintype "passive"))
      (node (ref "U4") (pin "14") (pinfunction "VBAT_14") (pintype "power_in"))
    )
    (net (code "55") (name "VUSB") (class "Default")
      (node (ref "J4") (pin "A4") (pinfunction "A4_A4") (pintype "bidirectional"))
      (node (ref "J4") (pin "A9") (pinfunction "A9_A9") (pintype "bidirectional"))
      (node (ref "J4") (pin "B4") (pinfunction "B4_B4") (pintype "bidirectional"))
      (node (ref "J4") (pin "B9") (pinfunction "B9_B9") (pintype "bidirectional"))
      (node (ref "R18") (pin "1") (pinfunction "1_1") (pintype "passive"))
    )
    (net (code "56") (name "unconnected-(IC1-NC-Pad4)") (class "Default")
      (node (ref "IC1") (pin "4") (pinfunction "NC_4") (pintype "no_connect"))
    )
    (net (code "57") (name "unconnected-(IC2-NC-Pad4)") (class "Default")
      (node (ref "IC2") (pin "4") (pinfunction "NC_4") (pintype "no_connect"))
    )
    (net (code "58") (name "unconnected-(J1-DAT1-PadP8)") (class "Default")
      (node (ref "J1") (pin "P8") (pinfunction "DAT1_P8") (pintype "bidirectional"))
    )
    (net (code "59") (name "unconnected-(J1-DAT2-PadP1)") (class "Default")
      (node (ref "J1") (pin "P1") (pinfunction "DAT2_P1") (pintype "bidirectional"))
    )
    (net (code "60") (name "unconnected-(J1-DETECTION_1-PadS1)") (class "Default")
      (node (ref "J1") (pin "S1") (pinfunction "DETECTION_1_S1") (pintype "bidirectional"))
    )
    (net (code "61") (name "unconnected-(J1-DETECTION_2-PadS2)") (class "Default")
      (node (ref "J1") (pin "S2") (pinfunction "DETECTION_2_S2") (pintype "bidirectional"))
    )
    (net (code "62") (name "unconnected-(J3-Pad1)") (class "Default")
      (node (ref "J3") (pin "1") (pinfunction "1_1") (pintype "bidirectional"))
    )
    (net (code "63") (name "unconnected-(J3-Pad6)") (class "Default")
      (node (ref "J3") (pin "6") (pinfunction "6_6") (pintype "bidirectional"))
    )
    (net (code "64") (name "unconnected-(J3-Pad7)") (class "Default")
      (node (ref "J3") (pin "7") (pinfunction "7_7") (pintype "bidirectional"))
    )
    (net (code "65") (name "unconnected-(J4-PadA8)") (class "Default")
      (node (ref "J4") (pin "A8") (pinfunction "A8_A8") (pintype "bidirectional"))
    )
    (net (code "66") (name "unconnected-(J4-PadB8)") (class "Default")
      (node (ref "J4") (pin "B8") (pinfunction "B8_B8") (pintype "bidirectional"))
    )
    (net (code "67") (name "unconnected-(U1-NC-Pad22)") (class "Default")
      (node (ref "U1") (pin "22") (pinfunction "NC_22") (pintype "no_connect"))
    )
    (net (code "68") (name "unconnected-(U2-~{ALERT}-Pad5)") (class "Default")
      (node (ref "U2") (pin "5") (pinfunction "~{ALERT}_5") (pintype "output"))
    )
  )
)
